# PA-HF_100W-VHF_60W.net
KiCad netlist of a schematic drawn in Altium Designer
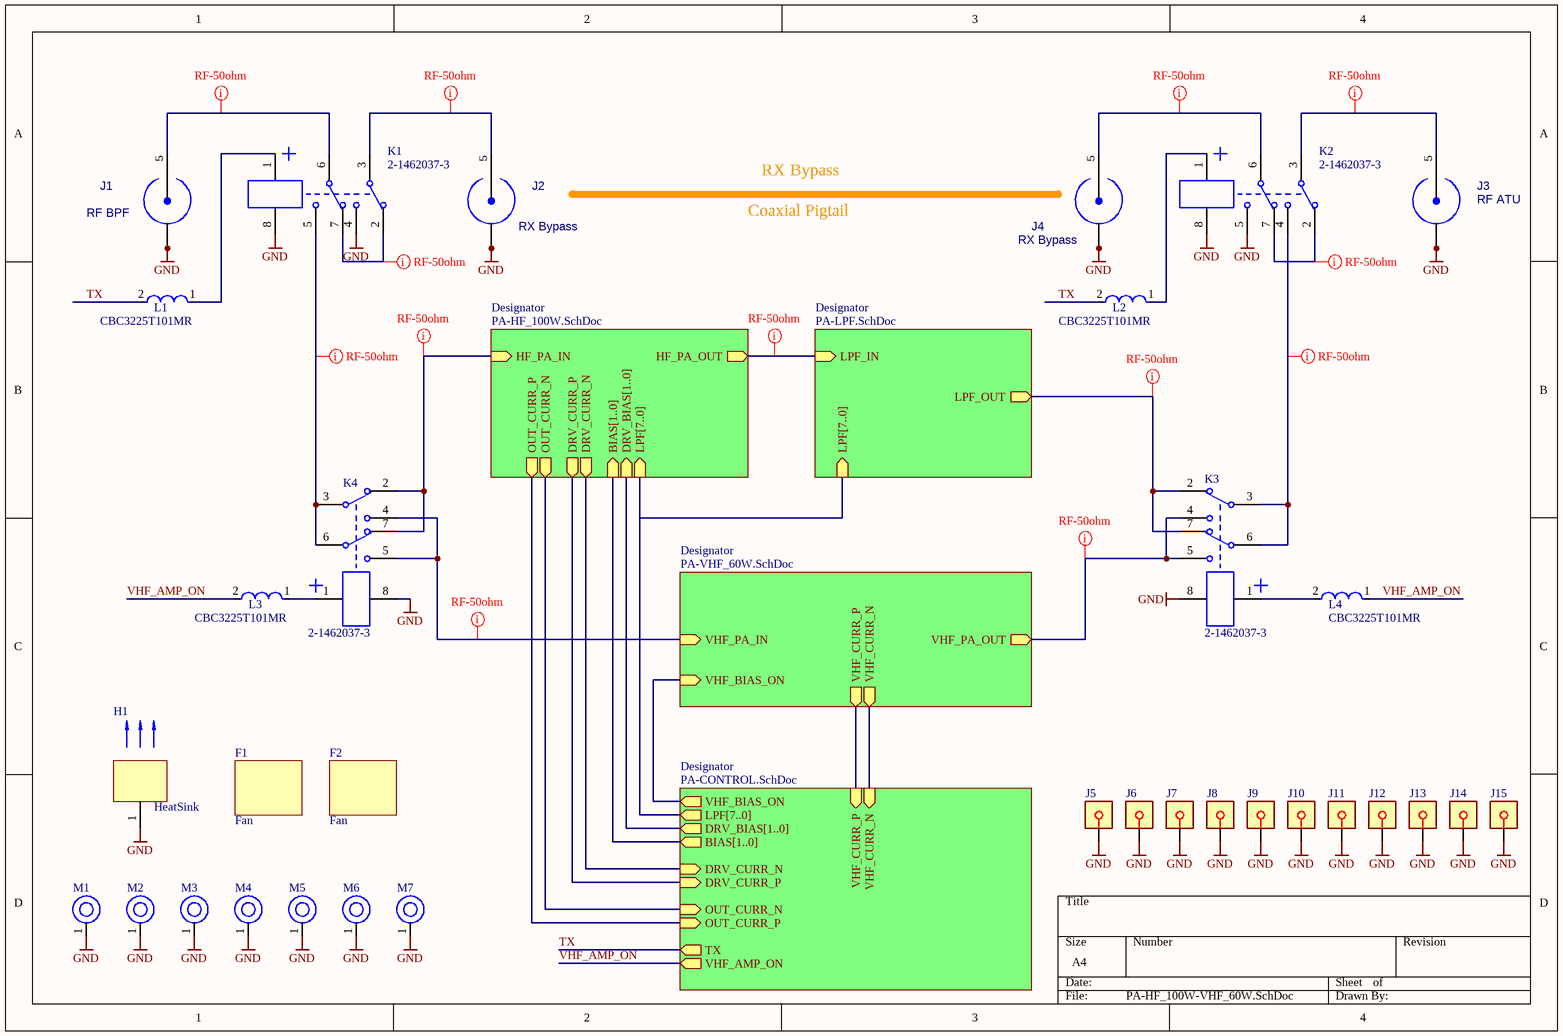
[diagram p0: PA-HF_100W-VHF_60W.SchDoc]

(export (version "E")
  (design (tool "Eeschema 10.0.6"))
  (components
    (comp (ref "F1") (value "Fan") (footprint "Fan_60x60x25mm") (libsource (lib "Hristo") (part "Fan")))
    (comp (ref "F2") (value "Fan") (footprint "Fan_60x60x25mm") (libsource (lib "Hristo") (part "Fan")))
    (comp (ref "H1")
      (value "HeatSink")
      (footprint "HEATSINK_145x140x35")
      (libsource (lib "Hristo") (part "HeatSink"))
    )
    (comp (ref "J1")
      (value "RF BPF")
      (footprint "31-5431")
      (description "SMA")
      (libsource (lib "RF-UNIT_1") (part "31-5431"))
    )
    (comp (ref "J2")
      (value "RX Bypass")
      (footprint "31-5431")
      (description "SMA")
      (libsource (lib "RF-UNIT_1") (part "31-5431"))
    )
    (comp (ref "J3")
      (value "RF ATU")
      (footprint "31-5431")
      (description "SMA")
      (libsource (lib "RF-UNIT_1") (part "31-5431"))
    )
    (comp (ref "J4")
      (value "RX Bypass")
      (footprint "31-5431")
      (description "SMA")
      (libsource (lib "RF-UNIT_1") (part "31-5431"))
    )
    (comp (ref "J5")
      (value "SMT RFI Shield Clip")
      (footprint "SMT RFI Shield Clip")
      (libsource (lib "Sch") (part "SMT RFI Shield Clip"))
    )
    (comp (ref "J6")
      (value "SMT RFI Shield Clip")
      (footprint "SMT RFI Shield Clip")
      (libsource (lib "Sch") (part "SMT RFI Shield Clip"))
    )
    (comp (ref "J7")
      (value "SMT RFI Shield Clip")
      (footprint "SMT RFI Shield Clip")
      (libsource (lib "Sch") (part "SMT RFI Shield Clip"))
    )
    (comp (ref "J8")
      (value "SMT RFI Shield Clip")
      (footprint "SMT RFI Shield Clip")
      (libsource (lib "Sch") (part "SMT RFI Shield Clip"))
    )
    (comp (ref "J9")
      (value "SMT RFI Shield Clip")
      (footprint "SMT RFI Shield Clip")
      (libsource (lib "Sch") (part "SMT RFI Shield Clip"))
    )
    (comp (ref "J10")
      (value "SMT RFI Shield Clip")
      (footprint "SMT RFI Shield Clip")
      (libsource (lib "Sch") (part "SMT RFI Shield Clip"))
    )
    (comp (ref "J11")
      (value "SMT RFI Shield Clip")
      (footprint "SMT RFI Shield Clip")
      (libsource (lib "Sch") (part "SMT RFI Shield Clip"))
    )
    (comp (ref "J12")
      (value "SMT RFI Shield Clip")
      (footprint "SMT RFI Shield Clip")
      (libsource (lib "Sch") (part "SMT RFI Shield Clip"))
    )
    (comp (ref "J13")
      (value "SMT RFI Shield Clip")
      (footprint "SMT RFI Shield Clip")
      (libsource (lib "Sch") (part "SMT RFI Shield Clip"))
    )
    (comp (ref "J14")
      (value "SMT RFI Shield Clip")
      (footprint "SMT RFI Shield Clip")
      (libsource (lib "Sch") (part "SMT RFI Shield Clip"))
    )
    (comp (ref "J15")
      (value "SMT RFI Shield Clip")
      (footprint "SMT RFI Shield Clip")
      (libsource (lib "Sch") (part "SMT RFI Shield Clip"))
    )
    (comp (ref "K1")
      (value "2-1462037-3")
      (footprint "TECO-2-1462037-3_V")
      (description "Signal Relay, 2 A, 12 VDC, -40 to 85 degC, 8-Pin SMD, RoHS, Tape and Reel")
      (fields (field (name "MANUFACTURER") "TE Connectivity"))
      (libsource (lib "Hristo") (part "CMP-2000-05409-1"))
    )
    (comp (ref "K2")
      (value "2-1462037-3")
      (footprint "TECO-2-1462037-3_V")
      (description "Signal Relay, 2 A, 12 VDC, -40 to 85 degC, 8-Pin SMD, RoHS, Tape and Reel")
      (fields (field (name "MANUFACTURER") "TE Connectivity"))
      (libsource (lib "Hristo") (part "CMP-2000-05409-1"))
    )
    (comp (ref "K3")
      (value "2-1462037-3")
      (footprint "TECO-2-1462037-3_V")
      (description "Signal Relay, 2 A, 12 VDC, -40 to 85 degC, 8-Pin SMD, RoHS, Tape and Reel")
      (fields (field (name "MANUFACTURER") "TE Connectivity"))
      (libsource (lib "Hristo") (part "CMP-2000-05409-1"))
    )
    (comp (ref "K4")
      (value "2-1462037-3")
      (footprint "TECO-2-1462037-3_V")
      (description "Signal Relay, 2 A, 12 VDC, -40 to 85 degC, 8-Pin SMD, RoHS, Tape and Reel")
      (fields (field (name "MANUFACTURER") "TE Connectivity"))
      (libsource (lib "Hristo") (part "CMP-2000-05409-1"))
    )
    (comp (ref "L1")
      (value "CBC3225T101MR")
      (footprint "FP-CB3225-MFG")
      (description "SMD Inductors 100uH ±20% 0.34A 1.82Ω 1210")
      (fields (field (name "TOLERANCE") "20%"))
      (libsource (lib "Altium Content Vault") (part "725321dda6339637d4d059423bc1c3c"))
    )
    (comp (ref "L2")
      (value "CBC3225T101MR")
      (footprint "FP-CB3225-MFG")
      (description "SMD Inductors 100uH ±20% 0.34A 1.82Ω 1210")
      (fields (field (name "TOLERANCE") "20%"))
      (libsource (lib "Altium Content Vault") (part "725321dda6339637d4d059423bc1c3c"))
    )
    (comp (ref "L3")
      (value "CBC3225T101MR")
      (footprint "FP-CB3225-MFG")
      (description "SMD Inductors 100uH ±20% 0.34A 1.82Ω 1210")
      (fields (field (name "TOLERANCE") "20%"))
      (libsource (lib "Altium Content Vault") (part "725321dda6339637d4d059423bc1c3c"))
    )
    (comp (ref "L4")
      (value "CBC3225T101MR")
      (footprint "FP-CB3225-MFG")
      (description "SMD Inductors 100uH ±20% 0.34A 1.82Ω 1210")
      (fields (field (name "TOLERANCE") "20%"))
      (libsource (lib "Altium Content Vault") (part "725321dda6339637d4d059423bc1c3c"))
    )
    (comp (ref "M1")
      (value "MountHole")
      (footprint "MountHole")
      (libsource (lib "Hristo") (part "MountHole"))
    )
    (comp (ref "M2")
      (value "MountHole")
      (footprint "MountHole")
      (libsource (lib "Hristo") (part "MountHole"))
    )
    (comp (ref "M3")
      (value "MountHole")
      (footprint "MountHole")
      (libsource (lib "Hristo") (part "MountHole"))
    )
    (comp (ref "M4")
      (value "MountHole")
      (footprint "MountHole")
      (libsource (lib "Hristo") (part "MountHole"))
    )
    (comp (ref "M5")
      (value "MountHole")
      (footprint "MountHole")
      (libsource (lib "Hristo") (part "MountHole"))
    )
    (comp (ref "M6")
      (value "MountHole")
      (footprint "MountHole")
      (libsource (lib "Hristo") (part "MountHole"))
    )
    (comp (ref "M7")
      (value "MountHole")
      (footprint "MountHole")
      (libsource (lib "Hristo") (part "MountHole"))
    )
  )
  (nets
    (net (code "5") (name "/HF_PA_IN") (class "Default")
      (node (ref "K4") (pin "2") (pinfunction "2_2") (pintype "passive"))
      (node (ref "K4") (pin "7") (pinfunction "7_7") (pintype "passive"))
    )
    (net (code "8") (name "/LPF_OUT") (class "Default")
      (node (ref "K3") (pin "2") (pinfunction "2_2") (pintype "passive"))
      (node (ref "K3") (pin "7") (pinfunction "7_7") (pintype "passive"))
    )
    (net (code "11") (name "/TX") (class "Default")
      (node (ref "L1") (pin "2") (pinfunction "2_2") (pintype "passive"))
      (node (ref "L2") (pin "2") (pinfunction "2_2") (pintype "passive"))
    )
    (net (code "12") (name "/VHF_AMP_ON") (class "Default")
      (node (ref "L3") (pin "2") (pinfunction "2_2") (pintype "passive"))
      (node (ref "L4") (pin "1") (pinfunction "1_1") (pintype "passive"))
    )
    (net (code "16") (name "/VHF_PA_IN") (class "Default")
      (node (ref "K4") (pin "4") (pinfunction "4_4") (pintype "passive"))
      (node (ref "K4") (pin "5") (pinfunction "5_5") (pintype "passive"))
    )
    (net (code "17") (name "/VHF_PA_OUT") (class "Default")
      (node (ref "K3") (pin "4") (pinfunction "4_4") (pintype "passive"))
      (node (ref "K3") (pin "5") (pinfunction "5_5") (pintype "passive"))
    )
    (net (code "18") (name "GND") (class "Default")
      (node (ref "H1") (pin "1") (pintype "power_in"))
      (node (ref "J1") (pin "1") (pinfunction "GND_1") (pintype "passive"))
      (node (ref "J1") (pin "2") (pinfunction "GND_2") (pintype "passive"))
      (node (ref "J1") (pin "3") (pinfunction "GND_3") (pintype "passive"))
      (node (ref "J1") (pin "4") (pinfunction "GND_4") (pintype "passive"))
      (node (ref "J10") (pin "1") (pintype "power_in"))
      (node (ref "J11") (pin "1") (pintype "power_in"))
      (node (ref "J12") (pin "1") (pintype "power_in"))
      (node (ref "J13") (pin "1") (pintype "power_in"))
      (node (ref "J14") (pin "1") (pintype "power_in"))
      (node (ref "J15") (pin "1") (pintype "power_in"))
      (node (ref "J2") (pin "1") (pinfunction "GND_1") (pintype "passive"))
      (node (ref "J2") (pin "2") (pinfunction "GND_2") (pintype "passive"))
      (node (ref "J2") (pin "3") (pinfunction "GND_3") (pintype "passive"))
      (node (ref "J2") (pin "4") (pinfunction "GND_4") (pintype "passive"))
      (node (ref "J3") (pin "1") (pinfunction "GND_1") (pintype "passive"))
      (node (ref "J3") (pin "2") (pinfunction "GND_2") (pintype "passive"))
      (node (ref "J3") (pin "3") (pinfunction "GND_3") (pintype "passive"))
      (node (ref "J3") (pin "4") (pinfunction "GND_4") (pintype "passive"))
      (node (ref "J4") (pin "1") (pinfunction "GND_1") (pintype "passive"))
      (node (ref "J4") (pin "2") (pinfunction "GND_2") (pintype "passive"))
      (node (ref "J4") (pin "3") (pinfunction "GND_3") (pintype "passive"))
      (node (ref "J4") (pin "4") (pinfunction "GND_4") (pintype "passive"))
      (node (ref "J5") (pin "1") (pintype "power_in"))
      (node (ref "J6") (pin "1") (pintype "power_in"))
      (node (ref "J7") (pin "1") (pintype "power_in"))
      (node (ref "J8") (pin "1") (pintype "power_in"))
      (node (ref "J9") (pin "1") (pintype "power_in"))
      (node (ref "K1") (pin "4") (pinfunction "4_4") (pintype "passive"))
      (node (ref "K1") (pin "8") (pinfunction "8_8") (pintype "passive"))
      (node (ref "K2") (pin "5") (pinfunction "5_5") (pintype "passive"))
      (node (ref "K2") (pin "8") (pinfunction "8_8") (pintype "passive"))
      (node (ref "K3") (pin "8") (pinfunction "8_8") (pintype "passive"))
      (node (ref "K4") (pin "8") (pinfunction "8_8") (pintype "passive"))
      (node (ref "M1") (pin "1") (pintype "passive"))
      (node (ref "M2") (pin "1") (pintype "passive"))
      (node (ref "M3") (pin "1") (pintype "passive"))
      (node (ref "M4") (pin "1") (pintype "passive"))
      (node (ref "M5") (pin "1") (pintype "passive"))
      (node (ref "M6") (pin "1") (pintype "passive"))
      (node (ref "M7") (pin "1") (pintype "passive"))
    )
    (net (code "19") (name "Net-(J1-CON)") (class "Default")
      (node (ref "J1") (pin "5") (pinfunction "CON_5") (pintype "passive"))
      (node (ref "K1") (pin "6") (pinfunction "6_6") (pintype "passive"))
    )
    (net (code "20") (name "Net-(J2-CON)") (class "Default")
      (node (ref "J2") (pin "5") (pinfunction "CON_5") (pintype "passive"))
      (node (ref "K1") (pin "3") (pinfunction "3_3") (pintype "passive"))
    )
    (net (code "21") (name "Net-(J3-CON)") (class "Default")
      (node (ref "J3") (pin "5") (pinfunction "CON_5") (pintype "passive"))
      (node (ref "K2") (pin "3") (pinfunction "3_3") (pintype "passive"))
    )
    (net (code "22") (name "Net-(J4-CON)") (class "Default")
      (node (ref "J4") (pin "5") (pinfunction "CON_5") (pintype "passive"))
      (node (ref "K2") (pin "6") (pinfunction "6_6") (pintype "passive"))
    )
    (net (code "23") (name "Net-(K1-Pad1)") (class "Default")
      (node (ref "K1") (pin "1") (pinfunction "1_1") (pintype "passive"))
      (node (ref "L1") (pin "1") (pinfunction "1_1") (pintype "passive"))
    )
    (net (code "24") (name "Net-(K1-Pad2)") (class "Default")
      (node (ref "K1") (pin "2") (pinfunction "2_2") (pintype "passive"))
      (node (ref "K1") (pin "7") (pinfunction "7_7") (pintype "passive"))
    )
    (net (code "25") (name "Net-(K1-Pad5)") (class "Default")
      (node (ref "K1") (pin "5") (pinfunction "5_5") (pintype "passive"))
      (node (ref "K4") (pin "3") (pinfunction "3_3") (pintype "passive"))
      (node (ref "K4") (pin "6") (pinfunction "6_6") (pintype "passive"))
    )
    (net (code "26") (name "Net-(K2-Pad1)") (class "Default")
      (node (ref "K2") (pin "1") (pinfunction "1_1") (pintype "passive"))
      (node (ref "L2") (pin "1") (pinfunction "1_1") (pintype "passive"))
    )
    (net (code "27") (name "Net-(K2-Pad2)") (class "Default")
      (node (ref "K2") (pin "2") (pinfunction "2_2") (pintype "passive"))
      (node (ref "K2") (pin "7") (pinfunction "7_7") (pintype "passive"))
    )
    (net (code "28") (name "Net-(K2-Pad4)") (class "Default")
      (node (ref "K2") (pin "4") (pinfunction "4_4") (pintype "passive"))
      (node (ref "K3") (pin "3") (pinfunction "3_3") (pintype "passive"))
      (node (ref "K3") (pin "6") (pinfunction "6_6") (pintype "passive"))
    )
    (net (code "29") (name "Net-(K3-Pad1)") (class "Default")
      (node (ref "K3") (pin "1") (pinfunction "1_1") (pintype "passive"))
      (node (ref "L4") (pin "2") (pinfunction "2_2") (pintype "passive"))
    )
    (net (code "30") (name "Net-(K4-Pad1)") (class "Default")
      (node (ref "K4") (pin "1") (pinfunction "1_1") (pintype "passive"))
      (node (ref "L3") (pin "1") (pinfunction "1_1") (pintype "passive"))
    )
  )
)
